# Sheet1.net
KiCad netlist of a schematic drawn in Altium Designer
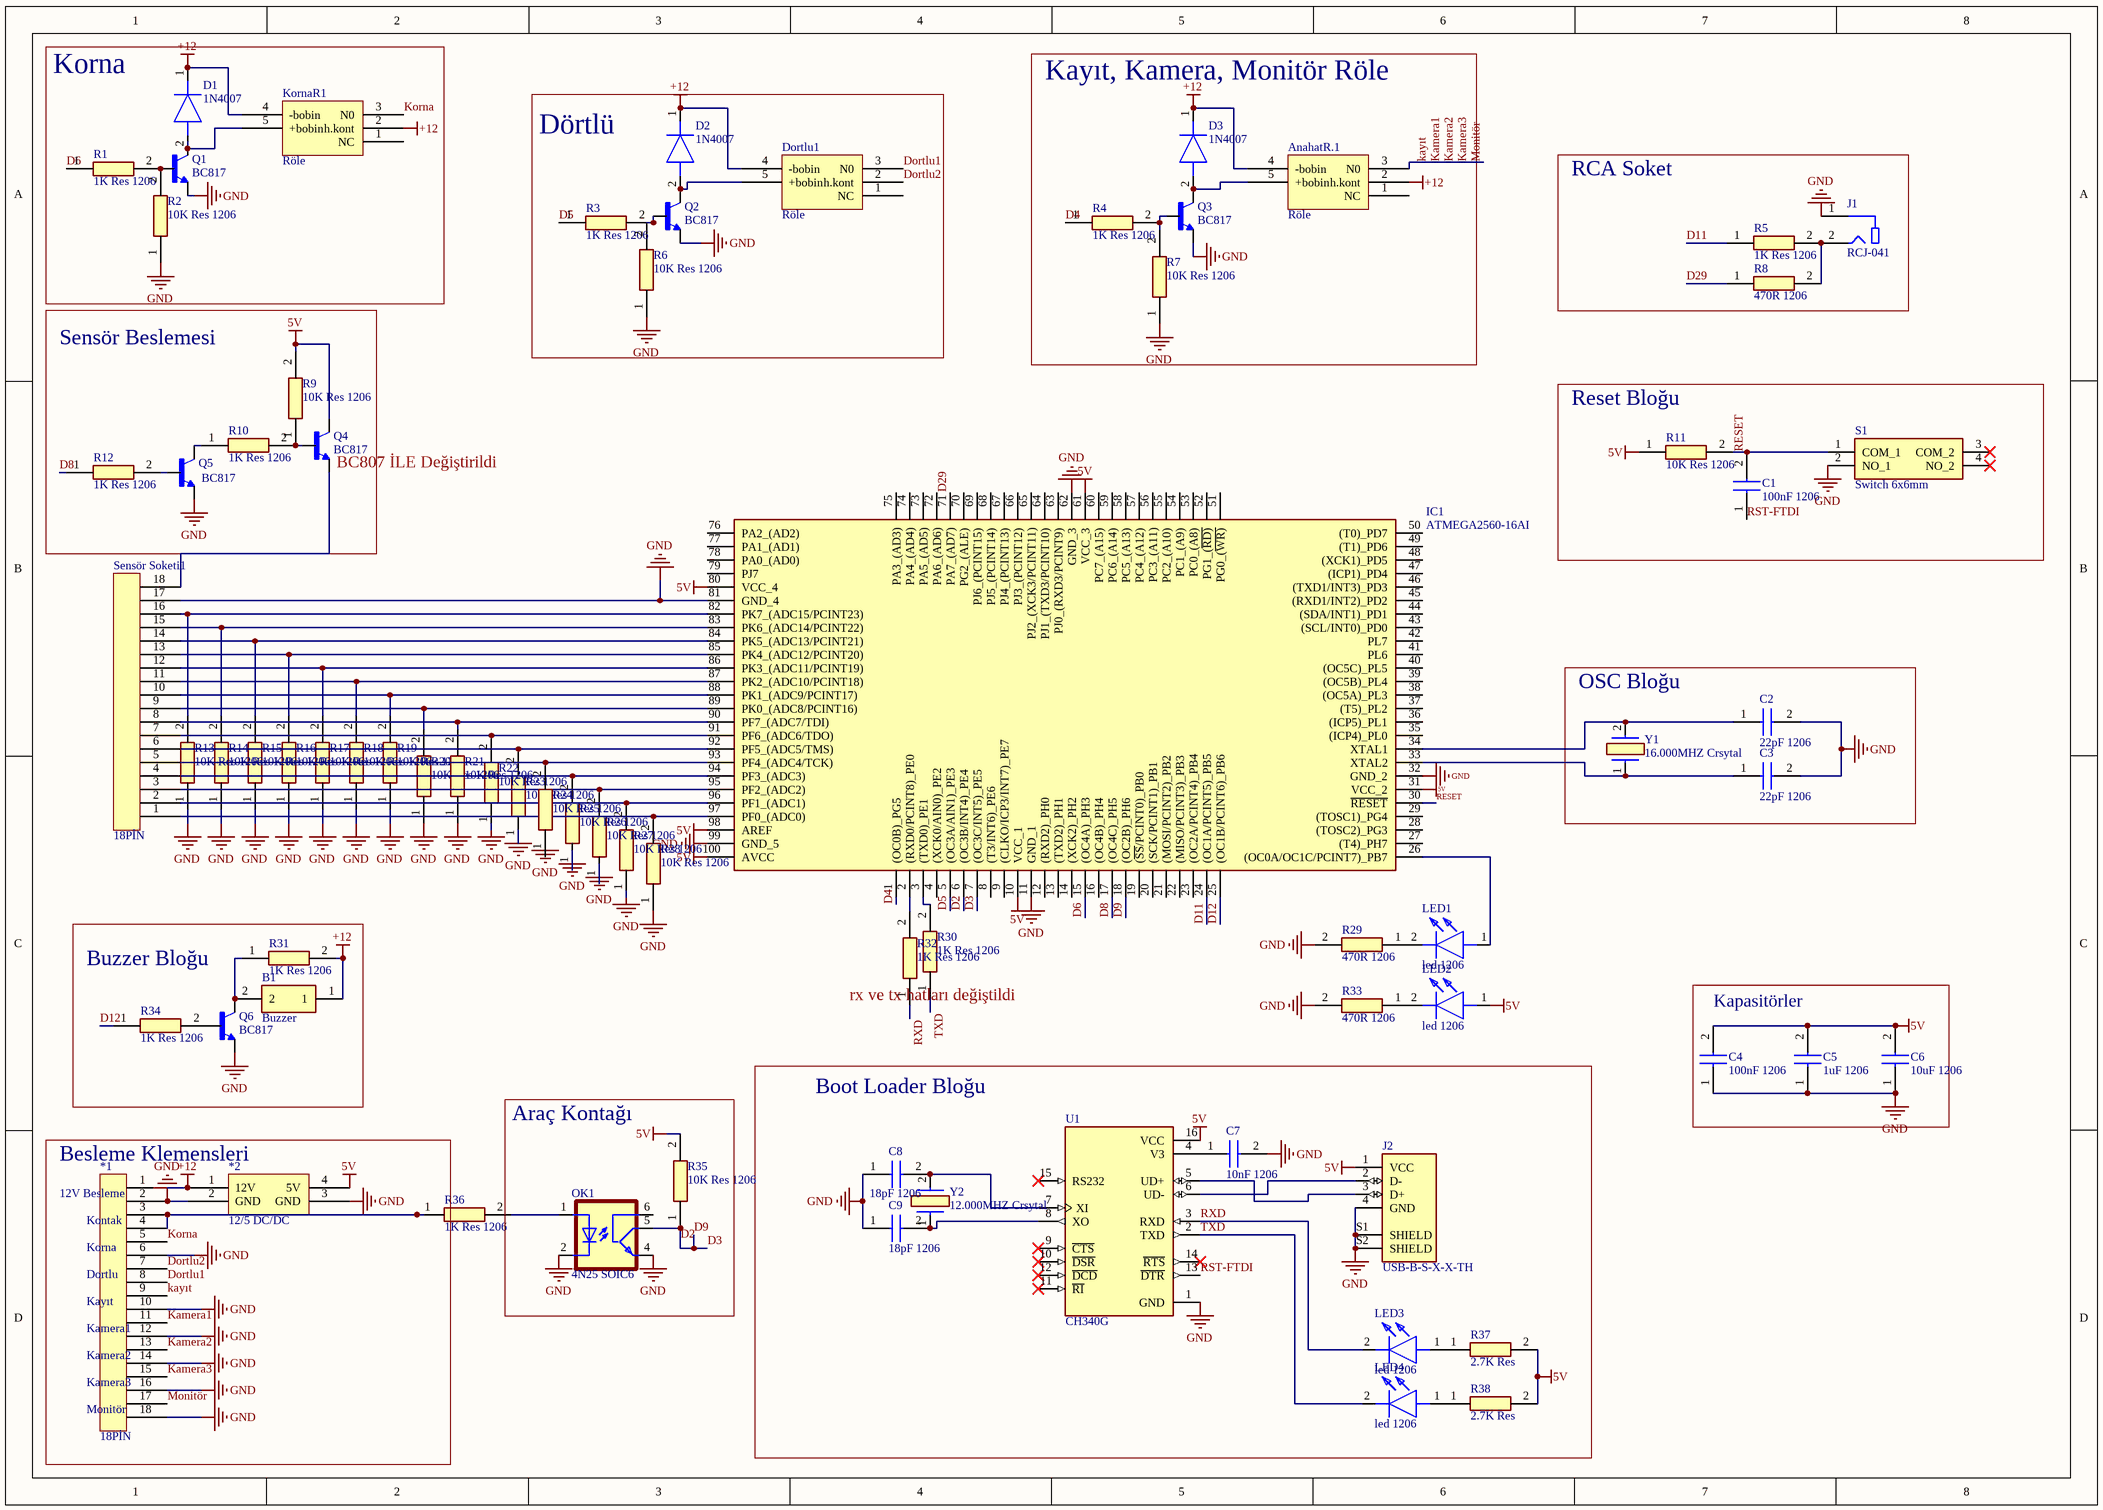
[diagram p0: Sheet1.SchDoc]

(export (version "E")
  (design (tool "Eeschema 10.0.6"))
  (components
    (comp (ref "*1") (value "18PİN") (footprint "18x5,08") (libsource (lib "Schlib1") (part "18PİN")))
    (comp (ref "*2")
      (value "12/5 DC/DC")
      (footprint "12/5V DC/DC")
      (libsource (lib "Schlib1") (part "12/5 DC/DC"))
    )
    (comp (ref "AnahatR.1") (value "Röle") (footprint "Röle") (libsource (lib "Schlib1") (part "Röle")))
    (comp (ref "B1")
      (value "Buzzer")
      (footprint "Buzzer")
      (description "TERMINAL BLOCK,HEADER, 5.08 MM, 2WAY; Product Range:-; Gender:Header")
      (fields (field (name "MF") "TE Connectivity") (field (name "MP") "282814-2"))
      (libsource (lib "Schlib1") (part "Buzzer"))
    )
    (comp (ref "C1")
      (value "100nF 1206")
      (footprint "CAPC3216X95N(100nF 1206)")
      (description "Capacitor")
      (fields
        (field (name "MANUFACTURER_PART_NUMBER") "GRM319F51H104ZA01D")
        (field (name "MOUSER PART NUMBER") "81-GRM319F51H104ZA")
      )
      (libsource (lib "Schlib1") (part "100nF 1206"))
    )
    (comp (ref "C2")
      (value "22pF 1206")
      (footprint "CAPC3216X95N(100nF 1206)")
      (description "Capacitor")
      (fields
        (field (name "MANUFACTURER_PART_NUMBER") "GRM319F51H104ZA01D")
        (field (name "MOUSER PART NUMBER") "81-GRM319F51H104ZA")
      )
      (libsource (lib "Schlib1") (part "22pF 1206"))
    )
    (comp (ref "C3")
      (value "22pF 1206")
      (footprint "CAPC3216X95N(100nF 1206)")
      (description "Capacitor")
      (fields
        (field (name "MANUFACTURER_PART_NUMBER") "GRM319F51H104ZA01D")
        (field (name "MOUSER PART NUMBER") "81-GRM319F51H104ZA")
      )
      (libsource (lib "Schlib1") (part "22pF 1206"))
    )
    (comp (ref "C4")
      (value "100nF 1206")
      (footprint "CAPC3216X95N(100nF 1206)")
      (description "Capacitor")
      (fields
        (field (name "MANUFACTURER_PART_NUMBER") "GRM319F51H104ZA01D")
        (field (name "MOUSER PART NUMBER") "81-GRM319F51H104ZA")
      )
      (libsource (lib "Schlib1") (part "100nF 1206"))
    )
    (comp (ref "C5")
      (value "1uF 1206")
      (footprint "CAPC3216X95N(100nF 1206)")
      (description "Capacitor")
      (fields
        (field (name "MANUFACTURER_PART_NUMBER") "GRM319F51H104ZA01D")
        (field (name "MOUSER PART NUMBER") "81-GRM319F51H104ZA")
      )
      (libsource (lib "Schlib1") (part "1uF 1206"))
    )
    (comp (ref "C6")
      (value "10uF 1206")
      (footprint "CAPC3216X95N(100nF 1206)")
      (description "Capacitor")
      (fields
        (field (name "MANUFACTURER_PART_NUMBER") "GRM319F51H104ZA01D")
        (field (name "MOUSER PART NUMBER") "81-GRM319F51H104ZA")
      )
      (libsource (lib "Schlib1") (part "10uF 1206"))
    )
    (comp (ref "C7")
      (value "10nF 1206")
      (footprint "CAPC3216X95N(100nF 1206)")
      (description "Capacitor")
      (fields
        (field (name "MANUFACTURER_PART_NUMBER") "GRM319F51H104ZA01D")
        (field (name "MOUSER PART NUMBER") "81-GRM319F51H104ZA")
      )
      (libsource (lib "Schlib1") (part "10nF 1206"))
    )
    (comp (ref "C8")
      (value "18pF 1206")
      (footprint "CAPC3216X95N(100nF 1206)")
      (description "Capacitor")
      (fields
        (field (name "MANUFACTURER_PART_NUMBER") "GRM319F51H104ZA01D")
        (field (name "MOUSER PART NUMBER") "81-GRM319F51H104ZA")
      )
      (libsource (lib "Schlib1") (part "18pF 1206"))
    )
    (comp (ref "C9")
      (value "18pF 1206")
      (footprint "CAPC3216X95N(100nF 1206)")
      (description "Capacitor")
      (fields
        (field (name "MANUFACTURER_PART_NUMBER") "GRM319F51H104ZA01D")
        (field (name "MOUSER PART NUMBER") "81-GRM319F51H104ZA")
      )
      (libsource (lib "Schlib1") (part "18pF 1206"))
    )
    (comp (ref "D1")
      (value "1N4007")
      (footprint "1N4007")
      (description "Diode")
      (fields
        (field (name "MANUFACTURER_PART_NUMBER") "1SS400SMT2R")
        (field (name "MOUSER PART NUMBER") "755-1SS400SMT2R")
      )
      (libsource (lib "Schlib1") (part "1N4007"))
    )
    (comp (ref "D2")
      (value "1N4007")
      (footprint "1N4007")
      (description "Diode")
      (fields
        (field (name "MANUFACTURER_PART_NUMBER") "1SS400SMT2R")
        (field (name "MOUSER PART NUMBER") "755-1SS400SMT2R")
      )
      (libsource (lib "Schlib1") (part "1N4007"))
    )
    (comp (ref "D3")
      (value "1N4007")
      (footprint "1N4007")
      (description "Diode")
      (fields
        (field (name "MANUFACTURER_PART_NUMBER") "1SS400SMT2R")
        (field (name "MOUSER PART NUMBER") "755-1SS400SMT2R")
      )
      (libsource (lib "Schlib1") (part "1N4007"))
    )
    (comp (ref "Dortlu1") (value "Röle") (footprint "Röle") (libsource (lib "Schlib1") (part "Röle")))
    (comp (ref "IC1")
      (value "ATMEGA2560-16AI")
      (footprint "QFP50P1600X1600X120-100N")
      (description "Integrated Circuit")
      (fields (field (name "MOUSER PART NUMBER") "556-ATMEGA2560-16AI"))
      (libsource (lib "Schlib1") (part "ATMEGA2560-16AI"))
    )
    (comp (ref "J1")
      (value "RCJ-041")
      (footprint "RCA")
      (description "Metal Right-Angle, RCA Jack, Black Housing and Insulation")
      (fields (field (name "MF") "CUI Devices"))
      (libsource (lib "Schlib1") (part "RCJ-041"))
    )
    (comp (ref "J2")
      (value "USB-B-S-X-X-TH")
      (footprint "USB-B-S-X-X-TH")
      (description "USB-B (USB TYPE-B) USB 2.0 Receptacle Connector 4 Position Through Hole, Right Angle")
      (libsource (lib "Schlib1") (part "USB-B-S-X-X-TH"))
    )
    (comp (ref "KornaR1") (value "Röle") (footprint "Röle") (libsource (lib "Schlib1") (part "Röle")))
    (comp (ref "LED1")
      (value "led 1206")
      (footprint "led 1206")
      (description "LED")
      (fields
        (field (name "MANUFACTURER_PART_NUMBER") "15412085A9000")
        (field (name "MOUSER PART NUMBER") "710-15412085A9000")
      )
      (libsource (lib "Schlib1") (part "led 1206"))
    )
    (comp (ref "LED2")
      (value "led 1206")
      (footprint "led 1206")
      (description "LED")
      (fields
        (field (name "MANUFACTURER_PART_NUMBER") "15412085A9000")
        (field (name "MOUSER PART NUMBER") "710-15412085A9000")
      )
      (libsource (lib "Schlib1") (part "led 1206"))
    )
    (comp (ref "LED3")
      (value "led 1206")
      (footprint "led 1206")
      (description "LED")
      (fields
        (field (name "MANUFACTURER_PART_NUMBER") "15412085A9000")
        (field (name "MOUSER PART NUMBER") "710-15412085A9000")
      )
      (libsource (lib "Schlib1") (part "led 1206"))
    )
    (comp (ref "LED4")
      (value "led 1206")
      (footprint "led 1206")
      (description "LED")
      (fields
        (field (name "MANUFACTURER_PART_NUMBER") "15412085A9000")
        (field (name "MOUSER PART NUMBER") "710-15412085A9000")
      )
      (libsource (lib "Schlib1") (part "led 1206"))
    )
    (comp (ref "OK1")
      (value "4N25 SOIC6")
      (footprint "4N25 SOIC6")
      (description "Optoisolator Transistor with Base Output 4170Vrms 1 Channel 6-SMD")
      (fields (field (name "MP") "4N25SM") (field (name "MF") "ON Semiconductor"))
      (libsource (lib "Schlib1") (part "4N25 SOIC6"))
    )
    (comp (ref "Q1")
      (value "BC817")
      (footprint "BC817 Sot23")
      (description "Bipolar _BJT_ Transistor NPN 45V 500mA 100MHz 300mW Surface Mount SOT-23-3 _TO-236_")
      (fields (field (name "MF") "Nexperia USA"))
      (libsource (lib "Schlib1") (part "BC817"))
    )
    (comp (ref "Q2")
      (value "BC817")
      (footprint "BC817 Sot23")
      (description "Bipolar _BJT_ Transistor NPN 45V 500mA 100MHz 300mW Surface Mount SOT-23-3 _TO-236_")
      (fields (field (name "MF") "Nexperia USA"))
      (libsource (lib "Schlib1") (part "BC817"))
    )
    (comp (ref "Q3")
      (value "BC817")
      (footprint "BC817 Sot23")
      (description "Bipolar _BJT_ Transistor NPN 45V 500mA 100MHz 300mW Surface Mount SOT-23-3 _TO-236_")
      (fields (field (name "MF") "Nexperia USA"))
      (libsource (lib "Schlib1") (part "BC817"))
    )
    (comp (ref "Q4")
      (value "BC817")
      (footprint "BC817 Sot23")
      (description "Bipolar _BJT_ Transistor NPN 45V 500mA 100MHz 300mW Surface Mount SOT-23-3 _TO-236_")
      (fields (field (name "MF") "Nexperia USA"))
      (libsource (lib "Schlib1") (part "BC817"))
    )
    (comp (ref "Q5")
      (value "BC817")
      (footprint "BC817 Sot23")
      (description "Bipolar _BJT_ Transistor NPN 45V 500mA 100MHz 300mW Surface Mount SOT-23-3 _TO-236_")
      (fields (field (name "MF") "Nexperia USA"))
      (libsource (lib "Schlib1") (part "BC817"))
    )
    (comp (ref "Q6")
      (value "BC817")
      (footprint "BC817 Sot23")
      (description "Bipolar _BJT_ Transistor NPN 45V 500mA 100MHz 300mW Surface Mount SOT-23-3 _TO-236_")
      (fields (field (name "MF") "Nexperia USA"))
      (libsource (lib "Schlib1") (part "BC817"))
    )
    (comp (ref "R1")
      (value "1K Res 1206")
      (footprint "RESC3216X60N ( 1206 )")
      (description "Resistor")
      (fields
        (field (name "MANUFACTURER_PART_NUMBER") "CRCW120610K0DHEAP")
        (field (name "MOUSER PART NUMBER") "71-CRCW120610K0DHEAP")
      )
      (libsource (lib "Schlib1") (part "1K Res 1206"))
    )
    (comp (ref "R2")
      (value "10K Res 1206")
      (footprint "RESC3216X60N ( 1206 )")
      (description "Resistor")
      (fields
        (field (name "MANUFACTURER_PART_NUMBER") "CRCW120610K0DHEAP")
        (field (name "MOUSER PART NUMBER") "71-CRCW120610K0DHEAP")
      )
      (libsource (lib "Schlib1") (part "10K Res 1206"))
    )
    (comp (ref "R3")
      (value "1K Res 1206")
      (footprint "RESC3216X60N ( 1206 )")
      (description "Resistor")
      (fields
        (field (name "MANUFACTURER_PART_NUMBER") "CRCW120610K0DHEAP")
        (field (name "MOUSER PART NUMBER") "71-CRCW120610K0DHEAP")
      )
      (libsource (lib "Schlib1") (part "1K Res 1206"))
    )
    (comp (ref "R4")
      (value "1K Res 1206")
      (footprint "RESC3216X60N ( 1206 )")
      (description "Resistor")
      (fields
        (field (name "MANUFACTURER_PART_NUMBER") "CRCW120610K0DHEAP")
        (field (name "MOUSER PART NUMBER") "71-CRCW120610K0DHEAP")
      )
      (libsource (lib "Schlib1") (part "1K Res 1206"))
    )
    (comp (ref "R5")
      (value "1K Res 1206")
      (footprint "RESC3216X60N ( 1206 )")
      (description "Resistor")
      (fields
        (field (name "MANUFACTURER_PART_NUMBER") "CRCW120610K0DHEAP")
        (field (name "MOUSER PART NUMBER") "71-CRCW120610K0DHEAP")
      )
      (libsource (lib "Schlib1") (part "1K Res 1206"))
    )
    (comp (ref "R6")
      (value "10K Res 1206")
      (footprint "RESC3216X60N ( 1206 )")
      (description "Resistor")
      (fields
        (field (name "MANUFACTURER_PART_NUMBER") "CRCW120610K0DHEAP")
        (field (name "MOUSER PART NUMBER") "71-CRCW120610K0DHEAP")
      )
      (libsource (lib "Schlib1") (part "10K Res 1206"))
    )
    (comp (ref "R7")
      (value "10K Res 1206")
      (footprint "RESC3216X60N ( 1206 )")
      (description "Resistor")
      (fields
        (field (name "MANUFACTURER_PART_NUMBER") "CRCW120610K0DHEAP")
        (field (name "MOUSER PART NUMBER") "71-CRCW120610K0DHEAP")
      )
      (libsource (lib "Schlib1") (part "10K Res 1206"))
    )
    (comp (ref "R8")
      (value "470R 1206")
      (footprint "RESC3216X60N ( 1206 )")
      (description "Resistor")
      (fields
        (field (name "MANUFACTURER_PART_NUMBER") "CRCW120610K0DHEAP")
        (field (name "MOUSER PART NUMBER") "71-CRCW120610K0DHEAP")
      )
      (libsource (lib "Schlib1") (part "470R 1206"))
    )
    (comp (ref "R9")
      (value "10K Res 1206")
      (footprint "RESC3216X60N ( 1206 )")
      (description "Resistor")
      (fields
        (field (name "MANUFACTURER_PART_NUMBER") "CRCW120610K0DHEAP")
        (field (name "MOUSER PART NUMBER") "71-CRCW120610K0DHEAP")
      )
      (libsource (lib "Schlib1") (part "10K Res 1206"))
    )
    (comp (ref "R10")
      (value "1K Res 1206")
      (footprint "RESC3216X60N ( 1206 )")
      (description "Resistor")
      (fields
        (field (name "MANUFACTURER_PART_NUMBER") "CRCW120610K0DHEAP")
        (field (name "MOUSER PART NUMBER") "71-CRCW120610K0DHEAP")
      )
      (libsource (lib "Schlib1") (part "1K Res 1206"))
    )
    (comp (ref "R11")
      (value "10K Res 1206")
      (footprint "RESC3216X60N ( 1206 )")
      (description "Resistor")
      (fields
        (field (name "MANUFACTURER_PART_NUMBER") "CRCW120610K0DHEAP")
        (field (name "MOUSER PART NUMBER") "71-CRCW120610K0DHEAP")
      )
      (libsource (lib "") (part "10K Res 1206_1"))
    )
    (comp (ref "R12")
      (value "1K Res 1206")
      (footprint "RESC3216X60N ( 1206 )")
      (description "Resistor")
      (fields
        (field (name "MANUFACTURER_PART_NUMBER") "CRCW120610K0DHEAP")
        (field (name "MOUSER PART NUMBER") "71-CRCW120610K0DHEAP")
      )
      (libsource (lib "Schlib1") (part "1K Res 1206"))
    )
    (comp (ref "R13")
      (value "10K Res 1206")
      (footprint "RESC3216X60N ( 1206 )")
      (description "Resistor")
      (fields
        (field (name "MANUFACTURER_PART_NUMBER") "CRCW120610K0DHEAP")
        (field (name "MOUSER PART NUMBER") "71-CRCW120610K0DHEAP")
      )
      (libsource (lib "Schlib1") (part "10K Res 1206"))
    )
    (comp (ref "R14")
      (value "10K Res 1206")
      (footprint "RESC3216X60N ( 1206 )")
      (description "Resistor")
      (fields
        (field (name "MANUFACTURER_PART_NUMBER") "CRCW120610K0DHEAP")
        (field (name "MOUSER PART NUMBER") "71-CRCW120610K0DHEAP")
      )
      (libsource (lib "Schlib1") (part "10K Res 1206"))
    )
    (comp (ref "R15")
      (value "10K Res 1206")
      (footprint "RESC3216X60N ( 1206 )")
      (description "Resistor")
      (fields
        (field (name "MANUFACTURER_PART_NUMBER") "CRCW120610K0DHEAP")
        (field (name "MOUSER PART NUMBER") "71-CRCW120610K0DHEAP")
      )
      (libsource (lib "Schlib1") (part "10K Res 1206"))
    )
    (comp (ref "R16")
      (value "10K Res 1206")
      (footprint "RESC3216X60N ( 1206 )")
      (description "Resistor")
      (fields
        (field (name "MANUFACTURER_PART_NUMBER") "CRCW120610K0DHEAP")
        (field (name "MOUSER PART NUMBER") "71-CRCW120610K0DHEAP")
      )
      (libsource (lib "Schlib1") (part "10K Res 1206"))
    )
    (comp (ref "R17")
      (value "10K Res 1206")
      (footprint "RESC3216X60N ( 1206 )")
      (description "Resistor")
      (fields
        (field (name "MANUFACTURER_PART_NUMBER") "CRCW120610K0DHEAP")
        (field (name "MOUSER PART NUMBER") "71-CRCW120610K0DHEAP")
      )
      (libsource (lib "Schlib1") (part "10K Res 1206"))
    )
    (comp (ref "R18")
      (value "10K Res 1206")
      (footprint "RESC3216X60N ( 1206 )")
      (description "Resistor")
      (fields
        (field (name "MANUFACTURER_PART_NUMBER") "CRCW120610K0DHEAP")
        (field (name "MOUSER PART NUMBER") "71-CRCW120610K0DHEAP")
      )
      (libsource (lib "Schlib1") (part "10K Res 1206"))
    )
    (comp (ref "R19")
      (value "10K Res 1206")
      (footprint "RESC3216X60N ( 1206 )")
      (description "Resistor")
      (fields
        (field (name "MANUFACTURER_PART_NUMBER") "CRCW120610K0DHEAP")
        (field (name "MOUSER PART NUMBER") "71-CRCW120610K0DHEAP")
      )
      (libsource (lib "Schlib1") (part "10K Res 1206"))
    )
    (comp (ref "R20")
      (value "10K Res 1206")
      (footprint "RESC3216X60N ( 1206 )")
      (description "Resistor")
      (fields
        (field (name "MANUFACTURER_PART_NUMBER") "CRCW120610K0DHEAP")
        (field (name "MOUSER PART NUMBER") "71-CRCW120610K0DHEAP")
      )
      (libsource (lib "Schlib1") (part "10K Res 1206"))
    )
    (comp (ref "R21")
      (value "10K Res 1206")
      (footprint "RESC3216X60N ( 1206 )")
      (description "Resistor")
      (fields
        (field (name "MANUFACTURER_PART_NUMBER") "CRCW120610K0DHEAP")
        (field (name "MOUSER PART NUMBER") "71-CRCW120610K0DHEAP")
      )
      (libsource (lib "Schlib1") (part "10K Res 1206"))
    )
    (comp (ref "R22")
      (value "10K Res 1206")
      (footprint "RESC3216X60N ( 1206 )")
      (description "Resistor")
      (fields
        (field (name "MANUFACTURER_PART_NUMBER") "CRCW120610K0DHEAP")
        (field (name "MOUSER PART NUMBER") "71-CRCW120610K0DHEAP")
      )
      (libsource (lib "Schlib1") (part "10K Res 1206"))
    )
    (comp (ref "R23")
      (value "10K Res 1206")
      (footprint "RESC3216X60N ( 1206 )")
      (description "Resistor")
      (fields
        (field (name "MANUFACTURER_PART_NUMBER") "CRCW120610K0DHEAP")
        (field (name "MOUSER PART NUMBER") "71-CRCW120610K0DHEAP")
      )
      (libsource (lib "Schlib1") (part "10K Res 1206"))
    )
    (comp (ref "R24")
      (value "10K Res 1206")
      (footprint "RESC3216X60N ( 1206 )")
      (description "Resistor")
      (fields
        (field (name "MANUFACTURER_PART_NUMBER") "CRCW120610K0DHEAP")
        (field (name "MOUSER PART NUMBER") "71-CRCW120610K0DHEAP")
      )
      (libsource (lib "Schlib1") (part "10K Res 1206"))
    )
    (comp (ref "R25")
      (value "10K Res 1206")
      (footprint "RESC3216X60N ( 1206 )")
      (description "Resistor")
      (fields
        (field (name "MANUFACTURER_PART_NUMBER") "CRCW120610K0DHEAP")
        (field (name "MOUSER PART NUMBER") "71-CRCW120610K0DHEAP")
      )
      (libsource (lib "Schlib1") (part "10K Res 1206"))
    )
    (comp (ref "R26")
      (value "10K Res 1206")
      (footprint "RESC3216X60N ( 1206 )")
      (description "Resistor")
      (fields
        (field (name "MANUFACTURER_PART_NUMBER") "CRCW120610K0DHEAP")
        (field (name "MOUSER PART NUMBER") "71-CRCW120610K0DHEAP")
      )
      (libsource (lib "Schlib1") (part "10K Res 1206"))
    )
    (comp (ref "R27")
      (value "10K Res 1206")
      (footprint "RESC3216X60N ( 1206 )")
      (description "Resistor")
      (fields
        (field (name "MANUFACTURER_PART_NUMBER") "CRCW120610K0DHEAP")
        (field (name "MOUSER PART NUMBER") "71-CRCW120610K0DHEAP")
      )
      (libsource (lib "Schlib1") (part "10K Res 1206"))
    )
    (comp (ref "R28")
      (value "10K Res 1206")
      (footprint "RESC3216X60N ( 1206 )")
      (description "Resistor")
      (fields
        (field (name "MANUFACTURER_PART_NUMBER") "CRCW120610K0DHEAP")
        (field (name "MOUSER PART NUMBER") "71-CRCW120610K0DHEAP")
      )
      (libsource (lib "Schlib1") (part "10K Res 1206"))
    )
    (comp (ref "R29")
      (value "470R 1206")
      (footprint "RESC3216X60N ( 1206 )")
      (description "Resistor")
      (fields
        (field (name "MANUFACTURER_PART_NUMBER") "CRCW120610K0DHEAP")
        (field (name "MOUSER PART NUMBER") "71-CRCW120610K0DHEAP")
      )
      (libsource (lib "") (part "470R 1206_1"))
    )
    (comp (ref "R30")
      (value "1K Res 1206")
      (footprint "RESC3216X60N ( 1206 )")
      (description "Resistor")
      (fields
        (field (name "MANUFACTURER_PART_NUMBER") "CRCW120610K0DHEAP")
        (field (name "MOUSER PART NUMBER") "71-CRCW120610K0DHEAP")
      )
      (libsource (lib "") (part "1K Res 1206_1"))
    )
    (comp (ref "R31")
      (value "1K Res 1206")
      (footprint "RESC3216X60N ( 1206 )")
      (description "Resistor")
      (fields
        (field (name "MANUFACTURER_PART_NUMBER") "CRCW120610K0DHEAP")
        (field (name "MOUSER PART NUMBER") "71-CRCW120610K0DHEAP")
      )
      (libsource (lib "Schlib1") (part "1K Res 1206"))
    )
    (comp (ref "R32")
      (value "1K Res 1206")
      (footprint "RESC3216X60N ( 1206 )")
      (description "Resistor")
      (fields
        (field (name "MANUFACTURER_PART_NUMBER") "CRCW120610K0DHEAP")
        (field (name "MOUSER PART NUMBER") "71-CRCW120610K0DHEAP")
      )
      (libsource (lib "") (part "1K Res 1206_1"))
    )
    (comp (ref "R33")
      (value "470R 1206")
      (footprint "RESC3216X60N ( 1206 )")
      (description "Resistor")
      (fields
        (field (name "MANUFACTURER_PART_NUMBER") "CRCW120610K0DHEAP")
        (field (name "MOUSER PART NUMBER") "71-CRCW120610K0DHEAP")
      )
      (libsource (lib "") (part "470R 1206_1"))
    )
    (comp (ref "R34")
      (value "1K Res 1206")
      (footprint "RESC3216X60N ( 1206 )")
      (description "Resistor")
      (fields
        (field (name "MANUFACTURER_PART_NUMBER") "CRCW120610K0DHEAP")
        (field (name "MOUSER PART NUMBER") "71-CRCW120610K0DHEAP")
      )
      (libsource (lib "Schlib1") (part "1K Res 1206"))
    )
    (comp (ref "R35")
      (value "10K Res 1206")
      (footprint "RESC3216X60N ( 1206 )")
      (description "Resistor")
      (fields
        (field (name "MANUFACTURER_PART_NUMBER") "CRCW120610K0DHEAP")
        (field (name "MOUSER PART NUMBER") "71-CRCW120610K0DHEAP")
      )
      (libsource (lib "Schlib1") (part "10K Res 1206"))
    )
    (comp (ref "R36")
      (value "1K Res 1206")
      (footprint "RESC3216X60N ( 1206 )")
      (description "Resistor")
      (fields
        (field (name "MANUFACTURER_PART_NUMBER") "CRCW120610K0DHEAP")
        (field (name "MOUSER PART NUMBER") "71-CRCW120610K0DHEAP")
      )
      (libsource (lib "Schlib1") (part "1K Res 1206"))
    )
    (comp (ref "R37")
      (value "2.7K Res")
      (footprint "RESC3216X60N ( 1206 )")
      (description "Resistor")
      (fields
        (field (name "MANUFACTURER_PART_NUMBER") "CRCW120610K0DHEAP")
        (field (name "MOUSER PART NUMBER") "71-CRCW120610K0DHEAP")
      )
      (libsource (lib "Schlib1") (part "2.7K Res"))
    )
    (comp (ref "R38")
      (value "2.7K Res")
      (footprint "RESC3216X60N ( 1206 )")
      (description "Resistor")
      (fields
        (field (name "MANUFACTURER_PART_NUMBER") "CRCW120610K0DHEAP")
        (field (name "MOUSER PART NUMBER") "71-CRCW120610K0DHEAP")
      )
      (libsource (lib "Schlib1") (part "2.7K Res"))
    )
    (comp (ref "S1")
      (value "Switch 6x6mm")
      (footprint "6x6x8mm Push Buton")
      (description "Switch")
      (fields
        (field (name "MANUFACTURER_PART_NUMBER") "430182070816")
        (field (name "MOUSER PART NUMBER") "710-430182070816")
      )
      (libsource (lib "Schlib1") (part "Switch 6x6mm"))
    )
    (comp (ref "Sensör Soketi1") (value "18PİN") (footprint "18x5,08") (libsource (lib "") (part "18PİN_1")))
    (comp (ref "U1") (value "CH340G") (footprint "SOIC16") (libsource (lib "Schlib1") (part "CH340G")))
    (comp (ref "Y1")
      (value "16.000MHZ Crsytal")
      (footprint "XTAL_Dip")
      (description "Crystal or Oscillator")
      (fields
        (field (name "MANUFACTURER_PART_NUMBER") "ABLS2-16.000MHZ-D4Y-T")
        (field (name "MOUSER PART NUMBER") "815-ABLS2-16-D4Y-T")
      )
      (libsource (lib "Schlib1") (part "16.000MHZ Crsytal"))
    )
    (comp (ref "Y2")
      (value "12.000MHZ Crsytal")
      (footprint "XTAL_Dip")
      (description "Crystal or Oscillator")
      (fields
        (field (name "MANUFACTURER_PART_NUMBER") "ABLS2-16.000MHZ-D4Y-T")
        (field (name "MOUSER PART NUMBER") "815-ABLS2-16-D4Y-T")
      )
      (libsource (lib "Schlib1") (part "12.000MHZ Crsytal"))
    )
  )
  (nets
    (net (code "1") (name "+12") (class "Default")
      (node (ref "*1") (pin "1") (pintype "passive"))
      (node (ref "*2") (pin "1") (pinfunction "12V_1") (pintype "passive"))
      (node (ref "AnahatR.1") (pin "2") (pinfunction "h.kont_2") (pintype "passive"))
      (node (ref "AnahatR.1") (pin "4") (pinfunction "-bobin_4") (pintype "passive"))
      (node (ref "B1") (pin "1") (pinfunction "1_1") (pintype "passive"))
      (node (ref "D1") (pin "1") (pinfunction "K_1") (pintype "passive"))
      (node (ref "D2") (pin "1") (pinfunction "K_1") (pintype "passive"))
      (node (ref "D3") (pin "1") (pinfunction "K_1") (pintype "passive"))
      (node (ref "Dortlu1") (pin "4") (pinfunction "-bobin_4") (pintype "passive"))
      (node (ref "KornaR1") (pin "2") (pinfunction "h.kont_2") (pintype "passive"))
      (node (ref "KornaR1") (pin "4") (pinfunction "-bobin_4") (pintype "passive"))
      (node (ref "R31") (pin "2") (pinfunction "2_2") (pintype "passive"))
    )
    (net (code "2") (name "/D2") (class "Default")
      (node (ref "IC1") (pin "18") (pinfunction "(OC2B)_PH6_18") (pintype "passive"))
      (node (ref "IC1") (pin "6") (pinfunction "(OC3B/INT4)_PE4_6") (pintype "passive"))
      (node (ref "IC1") (pin "7") (pinfunction "(OC3C/INT5)_PE5_7") (pintype "passive"))
      (node (ref "OK1") (pin "5") (pinfunction "COL_5") (pintype "passive"))
      (node (ref "R35") (pin "1") (pinfunction "1_1") (pintype "passive"))
    )
    (net (code "3") (name "/D4") (class "Default")
      (node (ref "IC1") (pin "1") (pinfunction "(OC0B)_PG5_1") (pintype "passive"))
      (node (ref "R4") (pin "1") (pinfunction "1_1") (pintype "passive"))
    )
    (net (code "4") (name "/D5") (class "Default")
      (node (ref "IC1") (pin "5") (pinfunction "(OC3A/AIN1)_PE3_5") (pintype "passive"))
      (node (ref "R3") (pin "1") (pinfunction "1_1") (pintype "passive"))
    )
    (net (code "5") (name "/D6") (class "Default")
      (node (ref "IC1") (pin "15") (pinfunction "(OC4A)_PH3_15") (pintype "passive"))
      (node (ref "R1") (pin "1") (pinfunction "1_1") (pintype "passive"))
    )
    (net (code "6") (name "/D8") (class "Default")
      (node (ref "IC1") (pin "17") (pinfunction "(OC4C)_PH5_17") (pintype "passive"))
      (node (ref "R12") (pin "1") (pinfunction "1_1") (pintype "passive"))
    )
    (net (code "7") (name "/D11") (class "Default")
      (node (ref "IC1") (pin "24") (pinfunction "(OC1A/PCINT5)_PB5_24") (pintype "passive"))
      (node (ref "R5") (pin "1") (pinfunction "1_1") (pintype "passive"))
    )
    (net (code "8") (name "/D12") (class "Default")
      (node (ref "IC1") (pin "25") (pinfunction "(OC1B/PCINT6)_PB6_25") (pintype "passive"))
      (node (ref "R34") (pin "1") (pinfunction "1_1") (pintype "passive"))
    )
    (net (code "9") (name "/D29") (class "Default")
      (node (ref "IC1") (pin "71") (pinfunction "PA7_(AD7)_71") (pintype "passive"))
      (node (ref "R8") (pin "1") (pinfunction "1_1") (pintype "passive"))
    )
    (net (code "10") (name "/Dortlu1") (class "Default")
      (node (ref "*1") (pin "8") (pintype "passive"))
      (node (ref "Dortlu1") (pin "3") (pinfunction "N0_3") (pintype "passive"))
    )
    (net (code "11") (name "/Dortlu2") (class "Default")
      (node (ref "*1") (pin "7") (pintype "passive"))
      (node (ref "Dortlu1") (pin "2") (pinfunction "h.kont_2") (pintype "passive"))
    )
    (net (code "12") (name "/Kamera1") (class "Default")
      (node (ref "*1") (pin "11") (pintype "passive"))
      (node (ref "*1") (pin "13") (pintype "passive"))
      (node (ref "*1") (pin "15") (pintype "passive"))
      (node (ref "*1") (pin "17") (pintype "passive"))
      (node (ref "*1") (pin "9") (pintype "passive"))
      (node (ref "AnahatR.1") (pin "3") (pinfunction "N0_3") (pintype "passive"))
    )
    (net (code "13") (name "/Korna") (class "Default")
      (node (ref "*1") (pin "5") (pintype "passive"))
      (node (ref "KornaR1") (pin "3") (pinfunction "N0_3") (pintype "passive"))
    )
    (net (code "14") (name "/RESET") (class "Default")
      (node (ref "C1") (pin "2") (pinfunction "2_2") (pintype "passive"))
      (node (ref "IC1") (pin "30") (pinfunction "~{RESET}_30") (pintype "passive"))
      (node (ref "R11") (pin "2") (pinfunction "2_2") (pintype "passive"))
      (node (ref "S1") (pin "1") (pinfunction "COM_1_1") (pintype "passive"))
    )
    (net (code "15") (name "/RST-FTDI") (class "Default")
      (node (ref "C1") (pin "1") (pinfunction "1_1") (pintype "passive"))
      (node (ref "U1") (pin "13") (pinfunction "~{DTR}_13") (pintype "output"))
    )
    (net (code "16") (name "/RXD") (class "Default")
      (node (ref "LED3") (pin "2") (pinfunction "K_2") (pintype "passive"))
      (node (ref "R32") (pin "1") (pinfunction "1_1") (pintype "passive"))
      (node (ref "U1") (pin "3") (pinfunction "RXD_3") (pintype "input"))
    )
    (net (code "17") (name "/TXD") (class "Default")
      (node (ref "LED4") (pin "2") (pinfunction "K_2") (pintype "passive"))
      (node (ref "R30") (pin "1") (pinfunction "1_1") (pintype "passive"))
      (node (ref "U1") (pin "2") (pinfunction "TXD_2") (pintype "output"))
    )
    (net (code "18") (name "5V") (class "Default")
      (node (ref "*2") (pin "4") (pinfunction "5V_4") (pintype "passive"))
      (node (ref "C4") (pin "2") (pinfunction "2_2") (pintype "passive"))
      (node (ref "C5") (pin "2") (pinfunction "2_2") (pintype "passive"))
      (node (ref "C6") (pin "2") (pinfunction "2_2") (pintype "passive"))
      (node (ref "IC1") (pin "10") (pinfunction "VCC_1_10") (pintype "passive"))
      (node (ref "IC1") (pin "100") (pinfunction "AVCC_100") (pintype "passive"))
      (node (ref "IC1") (pin "31") (pinfunction "VCC_2_31") (pintype "passive"))
      (node (ref "IC1") (pin "61") (pinfunction "VCC_3_61") (pintype "passive"))
      (node (ref "IC1") (pin "80") (pinfunction "VCC_4_80") (pintype "passive"))
      (node (ref "IC1") (pin "98") (pinfunction "AREF_98") (pintype "passive"))
      (node (ref "J2") (pin "1") (pinfunction "VCC_1") (pintype "power_in"))
      (node (ref "LED2") (pin "1") (pinfunction "A_1") (pintype "passive"))
      (node (ref "Q4") (pin "3") (pinfunction "C_3") (pintype "passive"))
      (node (ref "R11") (pin "1") (pinfunction "1_1") (pintype "passive"))
      (node (ref "R35") (pin "2") (pinfunction "2_2") (pintype "passive"))
      (node (ref "R37") (pin "2") (pinfunction "2_2") (pintype "passive"))
      (node (ref "R38") (pin "2") (pinfunction "2_2") (pintype "passive"))
      (node (ref "R9") (pin "2") (pinfunction "2_2") (pintype "passive"))
      (node (ref "U1") (pin "16") (pinfunction "VCC_16") (pintype "power_in"))
    )
    (net (code "19") (name "GND") (class "Default")
      (node (ref "*1") (pin "10") (pintype "passive"))
      (node (ref "*1") (pin "12") (pintype "passive"))
      (node (ref "*1") (pin "14") (pintype "passive"))
      (node (ref "*1") (pin "16") (pintype "passive"))
      (node (ref "*1") (pin "18") (pintype "passive"))
      (node (ref "*1") (pin "2") (pintype "passive"))
      (node (ref "*1") (pin "6") (pintype "passive"))
      (node (ref "*2") (pin "2") (pinfunction "GND_2") (pintype "passive"))
      (node (ref "*2") (pin "3") (pinfunction "GND_3") (pintype "passive"))
      (node (ref "C2") (pin "2") (pinfunction "2_2") (pintype "passive"))
      (node (ref "C3") (pin "2") (pinfunction "2_2") (pintype "passive"))
      (node (ref "C4") (pin "1") (pinfunction "1_1") (pintype "passive"))
      (node (ref "C5") (pin "1") (pinfunction "1_1") (pintype "passive"))
      (node (ref "C6") (pin "1") (pinfunction "1_1") (pintype "passive"))
      (node (ref "C7") (pin "2") (pinfunction "2_2") (pintype "passive"))
      (node (ref "C8") (pin "1") (pinfunction "1_1") (pintype "passive"))
      (node (ref "C9") (pin "1") (pinfunction "1_1") (pintype "passive"))
      (node (ref "IC1") (pin "11") (pinfunction "GND_1_11") (pintype "passive"))
      (node (ref "IC1") (pin "32") (pinfunction "GND_2_32") (pintype "passive"))
      (node (ref "IC1") (pin "62") (pinfunction "GND_3_62") (pintype "passive"))
      (node (ref "IC1") (pin "81") (pinfunction "GND_4_81") (pintype "passive"))
      (node (ref "IC1") (pin "99") (pinfunction "GND_5_99") (pintype "passive"))
      (node (ref "J1") (pin "1") (pinfunction "1_1") (pintype "passive"))
      (node (ref "J2") (pin "4") (pinfunction "GND_4") (pintype "power_in"))
      (node (ref "J2") (pin "S1") (pinfunction "SHIELD_S1") (pintype "passive"))
      (node (ref "J2") (pin "S2") (pinfunction "SHIELD_S2") (pintype "passive"))
      (node (ref "OK1") (pin "2") (pinfunction "C_2") (pintype "passive"))
      (node (ref "OK1") (pin "4") (pinfunction "EMI_4") (pintype "passive"))
      (node (ref "Q1") (pin "2") (pinfunction "E_2") (pintype "passive"))
      (node (ref "Q2") (pin "2") (pinfunction "E_2") (pintype "passive"))
      (node (ref "Q3") (pin "2") (pinfunction "E_2") (pintype "passive"))
      (node (ref "Q5") (pin "2") (pinfunction "E_2") (pintype "passive"))
      (node (ref "Q6") (pin "2") (pinfunction "E_2") (pintype "passive"))
      (node (ref "R13") (pin "1") (pinfunction "1_1") (pintype "passive"))
      (node (ref "R14") (pin "1") (pinfunction "1_1") (pintype "passive"))
      (node (ref "R15") (pin "1") (pinfunction "1_1") (pintype "passive"))
      (node (ref "R16") (pin "1") (pinfunction "1_1") (pintype "passive"))
      (node (ref "R17") (pin "1") (pinfunction "1_1") (pintype "passive"))
      (node (ref "R18") (pin "1") (pinfunction "1_1") (pintype "passive"))
      (node (ref "R19") (pin "1") (pinfunction "1_1") (pintype "passive"))
      (node (ref "R2") (pin "1") (pinfunction "1_1") (pintype "passive"))
      (node (ref "R20") (pin "1") (pinfunction "1_1") (pintype "passive"))
      (node (ref "R21") (pin "1") (pinfunction "1_1") (pintype "passive"))
      (node (ref "R22") (pin "1") (pinfunction "1_1") (pintype "passive"))
      (node (ref "R23") (pin "1") (pinfunction "1_1") (pintype "passive"))
      (node (ref "R24") (pin "1") (pinfunction "1_1") (pintype "passive"))
      (node (ref "R25") (pin "1") (pinfunction "1_1") (pintype "passive"))
      (node (ref "R26") (pin "1") (pinfunction "1_1") (pintype "passive"))
      (node (ref "R27") (pin "1") (pinfunction "1_1") (pintype "passive"))
      (node (ref "R28") (pin "1") (pinfunction "1_1") (pintype "passive"))
      (node (ref "R29") (pin "2") (pinfunction "2_2") (pintype "passive"))
      (node (ref "R33") (pin "2") (pinfunction "2_2") (pintype "passive"))
      (node (ref "R6") (pin "1") (pinfunction "1_1") (pintype "passive"))
      (node (ref "R7") (pin "1") (pinfunction "1_1") (pintype "passive"))
      (node (ref "S1") (pin "2") (pinfunction "NO_1_2") (pintype "passive"))
      (node (ref "Sensör Soketi1") (pin "17") (pintype "passive"))
      (node (ref "U1") (pin "1") (pinfunction "GND_1") (pintype "power_in"))
    )
    (net (code "20") (name "Net-(*1-Pad3)") (class "Default")
      (node (ref "*1") (pin "3") (pintype "passive"))
      (node (ref "*1") (pin "4") (pintype "passive"))
      (node (ref "R36") (pin "1") (pinfunction "1_1") (pintype "passive"))
    )
    (net (code "21") (name "Net-(AnahatR.1-+bobin)") (class "Default")
      (node (ref "AnahatR.1") (pin "5") (pinfunction "+bobin_5") (pintype "passive"))
      (node (ref "D3") (pin "2") (pinfunction "A_2") (pintype "passive"))
      (node (ref "Q3") (pin "3") (pinfunction "C_3") (pintype "passive"))
    )
    (net (code "22") (name "Net-(D1-A)") (class "Default")
      (node (ref "D1") (pin "2") (pinfunction "A_2") (pintype "passive"))
      (node (ref "KornaR1") (pin "5") (pinfunction "+bobin_5") (pintype "passive"))
      (node (ref "Q1") (pin "3") (pinfunction "C_3") (pintype "passive"))
    )
    (net (code "23") (name "Net-(D2-A)") (class "Default")
      (node (ref "D2") (pin "2") (pinfunction "A_2") (pintype "passive"))
      (node (ref "Dortlu1") (pin "5") (pinfunction "+bobin_5") (pintype "passive"))
      (node (ref "Q2") (pin "3") (pinfunction "C_3") (pintype "passive"))
    )
    (net (code "24") (name "Net-(IC1-(OC0A{slash}OC1C{slash}PCINT7)_PB7)") (class "Default")
      (node (ref "IC1") (pin "26") (pinfunction "(OC0A/OC1C/PCINT7)_PB7_26") (pintype "passive"))
      (node (ref "LED1") (pin "1") (pinfunction "A_1") (pintype "passive"))
    )
    (net (code "25") (name "Net-(IC1-(RXD0{slash}PCINT8)_PE0)") (class "Default")
      (node (ref "IC1") (pin "2") (pinfunction "(RXD0/PCINT8)_PE0_2") (pintype "passive"))
      (node (ref "R32") (pin "2") (pinfunction "2_2") (pintype "passive"))
    )
    (net (code "26") (name "Net-(IC1-(TXD0)_PE1)") (class "Default")
      (node (ref "IC1") (pin "3") (pinfunction "(TXD0)_PE1_3") (pintype "passive"))
      (node (ref "R30") (pin "2") (pinfunction "2_2") (pintype "passive"))
    )
    (net (code "27") (name "Net-(IC1-PF0_(ADC0))") (class "Default")
      (node (ref "IC1") (pin "97") (pinfunction "PF0_(ADC0)_97") (pintype "passive"))
      (node (ref "R28") (pin "2") (pinfunction "2_2") (pintype "passive"))
      (node (ref "Sensör Soketi1") (pin "1") (pintype "passive"))
    )
    (net (code "28") (name "Net-(IC1-PF1_(ADC1))") (class "Default")
      (node (ref "IC1") (pin "96") (pinfunction "PF1_(ADC1)_96") (pintype "passive"))
      (node (ref "R27") (pin "2") (pinfunction "2_2") (pintype "passive"))
      (node (ref "Sensör Soketi1") (pin "2") (pintype "passive"))
    )
    (net (code "29") (name "Net-(IC1-PF2_(ADC2))") (class "Default")
      (node (ref "IC1") (pin "95") (pinfunction "PF2_(ADC2)_95") (pintype "passive"))
      (node (ref "R26") (pin "2") (pinfunction "2_2") (pintype "passive"))
      (node (ref "Sensör Soketi1") (pin "3") (pintype "passive"))
    )
    (net (code "30") (name "Net-(IC1-PF3_(ADC3))") (class "Default")
      (node (ref "IC1") (pin "94") (pinfunction "PF3_(ADC3)_94") (pintype "passive"))
      (node (ref "R25") (pin "2") (pinfunction "2_2") (pintype "passive"))
      (node (ref "Sensör Soketi1") (pin "4") (pintype "passive"))
    )
    (net (code "31") (name "Net-(IC1-PF4_(ADC4{slash}TCK))") (class "Default")
      (node (ref "IC1") (pin "93") (pinfunction "PF4_(ADC4/TCK)_93") (pintype "passive"))
      (node (ref "R24") (pin "2") (pinfunction "2_2") (pintype "passive"))
      (node (ref "Sensör Soketi1") (pin "5") (pintype "passive"))
    )
    (net (code "32") (name "Net-(IC1-PF5_(ADC5{slash}TMS))") (class "Default")
      (node (ref "IC1") (pin "92") (pinfunction "PF5_(ADC5/TMS)_92") (pintype "passive"))
      (node (ref "R23") (pin "2") (pinfunction "2_2") (pintype "passive"))
      (node (ref "Sensör Soketi1") (pin "6") (pintype "passive"))
    )
    (net (code "33") (name "Net-(IC1-PF6_(ADC6{slash}TDO))") (class "Default")
      (node (ref "IC1") (pin "91") (pinfunction "PF6_(ADC6/TDO)_91") (pintype "passive"))
      (node (ref "R22") (pin "2") (pinfunction "2_2") (pintype "passive"))
      (node (ref "Sensör Soketi1") (pin "7") (pintype "passive"))
    )
    (net (code "34") (name "Net-(IC1-PF7_(ADC7{slash}TDI))") (class "Default")
      (node (ref "IC1") (pin "90") (pinfunction "PF7_(ADC7/TDI)_90") (pintype "passive"))
      (node (ref "R21") (pin "2") (pinfunction "2_2") (pintype "passive"))
      (node (ref "Sensör Soketi1") (pin "8") (pintype "passive"))
    )
    (net (code "35") (name "Net-(IC1-PK0_(ADC8{slash}PCINT16))") (class "Default")
      (node (ref "IC1") (pin "89") (pinfunction "PK0_(ADC8/PCINT16)_89") (pintype "passive"))
      (node (ref "R20") (pin "2") (pinfunction "2_2") (pintype "passive"))
      (node (ref "Sensör Soketi1") (pin "9") (pintype "passive"))
    )
    (net (code "36") (name "Net-(IC1-PK1_(ADC9{slash}PCINT17))") (class "Default")
      (node (ref "IC1") (pin "88") (pinfunction "PK1_(ADC9/PCINT17)_88") (pintype "passive"))
      (node (ref "R19") (pin "2") (pinfunction "2_2") (pintype "passive"))
      (node (ref "Sensör Soketi1") (pin "10") (pintype "passive"))
    )
    (net (code "37") (name "Net-(IC1-PK2_(ADC10{slash}PCINT18))") (class "Default")
      (node (ref "IC1") (pin "87") (pinfunction "PK2_(ADC10/PCINT18)_87") (pintype "passive"))
      (node (ref "R18") (pin "2") (pinfunction "2_2") (pintype "passive"))
      (node (ref "Sensör Soketi1") (pin "11") (pintype "passive"))
    )
    (net (code "38") (name "Net-(IC1-PK3_(ADC11{slash}PCINT19))") (class "Default")
      (node (ref "IC1") (pin "86") (pinfunction "PK3_(ADC11/PCINT19)_86") (pintype "passive"))
      (node (ref "R17") (pin "2") (pinfunction "2_2") (pintype "passive"))
      (node (ref "Sensör Soketi1") (pin "12") (pintype "passive"))
    )
    (net (code "39") (name "Net-(IC1-PK4_(ADC12{slash}PCINT20))") (class "Default")
      (node (ref "IC1") (pin "85") (pinfunction "PK4_(ADC12/PCINT20)_85") (pintype "passive"))
      (node (ref "R16") (pin "2") (pinfunction "2_2") (pintype "passive"))
      (node (ref "Sensör Soketi1") (pin "13") (pintype "passive"))
    )
    (net (code "40") (name "Net-(IC1-PK5_(ADC13{slash}PCINT21))") (class "Default")
      (node (ref "IC1") (pin "84") (pinfunction "PK5_(ADC13/PCINT21)_84") (pintype "passive"))
      (node (ref "R15") (pin "2") (pinfunction "2_2") (pintype "passive"))
      (node (ref "Sensör Soketi1") (pin "14") (pintype "passive"))
    )
    (net (code "41") (name "Net-(IC1-PK6_(ADC14{slash}PCINT22))") (class "Default")
      (node (ref "IC1") (pin "83") (pinfunction "PK6_(ADC14/PCINT22)_83") (pintype "passive"))
      (node (ref "R14") (pin "2") (pinfunction "2_2") (pintype "passive"))
      (node (ref "Sensör Soketi1") (pin "15") (pintype "passive"))
    )
    (net (code "42") (name "Net-(IC1-PK7_(ADC15{slash}PCINT23))") (class "Default")
      (node (ref "IC1") (pin "82") (pinfunction "PK7_(ADC15/PCINT23)_82") (pintype "passive"))
      (node (ref "R13") (pin "2") (pinfunction "2_2") (pintype "passive"))
      (node (ref "Sensör Soketi1") (pin "16") (pintype "passive"))
    )
    (net (code "43") (name "Net-(IC1-XTAL1)") (class "Default")
      (node (ref "C2") (pin "1") (pinfunction "1_1") (pintype "passive"))
      (node (ref "IC1") (pin "34") (pinfunction "XTAL1_34") (pintype "passive"))
      (node (ref "Y1") (pin "2") (pinfunction "2_2") (pintype "passive"))
    )
    (net (code "44") (name "Net-(IC1-XTAL2)") (class "Default")
      (node (ref "C3") (pin "1") (pinfunction "1_1") (pintype "passive"))
      (node (ref "IC1") (pin "33") (pinfunction "XTAL2_33") (pintype "passive"))
      (node (ref "Y1") (pin "1") (pinfunction "1_1") (pintype "passive"))
    )
    (net (code "45") (name "Net-(J1-Pad2)") (class "Default")
      (node (ref "J1") (pin "2") (pinfunction "2_2") (pintype "passive"))
      (node (ref "R5") (pin "2") (pinfunction "2_2") (pintype "passive"))
      (node (ref "R8") (pin "2") (pinfunction "2_2") (pintype "passive"))
    )
    (net (code "46") (name "Net-(J2-D+)") (class "Default")
      (node (ref "J2") (pin "3") (pinfunction "D+_3") (pintype "bidirectional"))
      (node (ref "U1") (pin "5") (pinfunction "UD+_5") (pintype "bidirectional"))
    )
    (net (code "47") (name "Net-(J2-D-)") (class "Default")
      (node (ref "J2") (pin "2") (pinfunction "D-_2") (pintype "bidirectional"))
      (node (ref "U1") (pin "6") (pinfunction "UD-_6") (pintype "bidirectional"))
    )
    (net (code "48") (name "Net-(LED1-K)") (class "Default")
      (node (ref "LED1") (pin "2") (pinfunction "K_2") (pintype "passive"))
      (node (ref "R29") (pin "1") (pinfunction "1_1") (pintype "passive"))
    )
    (net (code "49") (name "Net-(LED2-K)") (class "Default")
      (node (ref "LED2") (pin "2") (pinfunction "K_2") (pintype "passive"))
      (node (ref "R33") (pin "1") (pinfunction "1_1") (pintype "passive"))
    )
    (net (code "50") (name "Net-(LED3-A)") (class "Default")
      (node (ref "LED3") (pin "1") (pinfunction "A_1") (pintype "passive"))
      (node (ref "R37") (pin "1") (pinfunction "1_1") (pintype "passive"))
    )
    (net (code "51") (name "Net-(LED4-A)") (class "Default")
      (node (ref "LED4") (pin "1") (pinfunction "A_1") (pintype "passive"))
      (node (ref "R38") (pin "1") (pinfunction "1_1") (pintype "passive"))
    )
    (net (code "52") (name "Net-(OK1-A)") (class "Default")
      (node (ref "OK1") (pin "1") (pinfunction "A_1") (pintype "passive"))
      (node (ref "R36") (pin "2") (pinfunction "2_2") (pintype "passive"))
    )
    (net (code "53") (name "Net-(Q1-B)") (class "Default")
      (node (ref "Q1") (pin "1") (pinfunction "B_1") (pintype "passive"))
      (node (ref "R1") (pin "2") (pinfunction "2_2") (pintype "passive"))
      (node (ref "R2") (pin "2") (pinfunction "2_2") (pintype "passive"))
    )
    (net (code "54") (name "Net-(Q2-B)") (class "Default")
      (node (ref "Q2") (pin "1") (pinfunction "B_1") (pintype "passive"))
      (node (ref "R3") (pin "2") (pinfunction "2_2") (pintype "passive"))
      (node (ref "R6") (pin "2") (pinfunction "2_2") (pintype "passive"))
    )
    (net (code "55") (name "Net-(Q3-B)") (class "Default")
      (node (ref "Q3") (pin "1") (pinfunction "B_1") (pintype "passive"))
      (node (ref "R4") (pin "2") (pinfunction "2_2") (pintype "passive"))
      (node (ref "R7") (pin "2") (pinfunction "2_2") (pintype "passive"))
    )
    (net (code "56") (name "Net-(Q4-B)") (class "Default")
      (node (ref "Q4") (pin "1") (pinfunction "B_1") (pintype "passive"))
      (node (ref "R10") (pin "2") (pinfunction "2_2") (pintype "passive"))
      (node (ref "R9") (pin "1") (pinfunction "1_1") (pintype "passive"))
    )
    (net (code "57") (name "Net-(Q4-E)") (class "Default")
      (node (ref "Q4") (pin "2") (pinfunction "E_2") (pintype "passive"))
      (node (ref "Sensör Soketi1") (pin "18") (pintype "passive"))
    )
    (net (code "58") (name "Net-(Q5-B)") (class "Default")
      (node (ref "Q5") (pin "1") (pinfunction "B_1") (pintype "passive"))
      (node (ref "R12") (pin "2") (pinfunction "2_2") (pintype "passive"))
    )
    (net (code "59") (name "Net-(Q5-C)") (class "Default")
      (node (ref "Q5") (pin "3") (pinfunction "C_3") (pintype "passive"))
      (node (ref "R10") (pin "1") (pinfunction "1_1") (pintype "passive"))
    )
    (net (code "60") (name "Net-(Q6-B)") (class "Default")
      (node (ref "Q6") (pin "1") (pinfunction "B_1") (pintype "passive"))
      (node (ref "R34") (pin "2") (pinfunction "2_2") (pintype "passive"))
    )
    (net (code "61") (name "Net-(Q6-C)") (class "Default")
      (node (ref "B1") (pin "2") (pinfunction "2_2") (pintype "passive"))
      (node (ref "Q6") (pin "3") (pinfunction "C_3") (pintype "passive"))
      (node (ref "R31") (pin "1") (pinfunction "1_1") (pintype "passive"))
    )
    (net (code "62") (name "Net-(U1-V3)") (class "Default")
      (node (ref "C7") (pin "1") (pinfunction "1_1") (pintype "passive"))
      (node (ref "U1") (pin "4") (pinfunction "V3_4") (pintype "power_in"))
    )
    (net (code "63") (name "Net-(U1-XI)") (class "Default")
      (node (ref "C8") (pin "2") (pinfunction "2_2") (pintype "passive"))
      (node (ref "U1") (pin "7") (pinfunction "XI_7") (pintype "input"))
      (node (ref "Y2") (pin "2") (pinfunction "2_2") (pintype "passive"))
    )
    (net (code "64") (name "Net-(U1-XO)") (class "Default")
      (node (ref "C9") (pin "2") (pinfunction "2_2") (pintype "passive"))
      (node (ref "U1") (pin "8") (pinfunction "XO_8") (pintype "output"))
      (node (ref "Y2") (pin "1") (pinfunction "1_1") (pintype "passive"))
    )
    (net (code "65") (name "unconnected-(AnahatR.1-NC-Pad1)") (class "Default")
      (node (ref "AnahatR.1") (pin "1") (pinfunction "NC_1") (pintype "passive"))
    )
    (net (code "66") (name "unconnected-(Dortlu1-NC-Pad1)") (class "Default")
      (node (ref "Dortlu1") (pin "1") (pinfunction "NC_1") (pintype "passive"))
    )
    (net (code "67") (name "unconnected-(IC1-(CLKO{slash}ICP3{slash}INT7)_PE7-Pad9)") (class "Default")
      (node (ref "IC1") (pin "9") (pinfunction "(CLKO/ICP3/INT7)_PE7_9") (pintype "passive"))
    )
    (net (code "68") (name "unconnected-(IC1-(ICP1)_PD4-Pad47)") (class "Default")
      (node (ref "IC1") (pin "47") (pinfunction "(ICP1)_PD4_47") (pintype "passive"))
    )
    (net (code "69") (name "unconnected-(IC1-(ICP4)_PL0-Pad35)") (class "Default")
      (node (ref "IC1") (pin "35") (pinfunction "(ICP4)_PL0_35") (pintype "passive"))
    )
    (net (code "70") (name "unconnected-(IC1-(ICP5)_PL1-Pad36)") (class "Default")
      (node (ref "IC1") (pin "36") (pinfunction "(ICP5)_PL1_36") (pintype "passive"))
    )
    (net (code "71") (name "unconnected-(IC1-(MISO{slash}PCINT3)_PB3-Pad22)") (class "Default")
      (node (ref "IC1") (pin "22") (pinfunction "(MISO/PCINT3)_PB3_22") (pintype "passive"))
    )
    (net (code "72") (name "unconnected-(IC1-(MOSI{slash}PCINT2)_PB2-Pad21)") (class "Default")
      (node (ref "IC1") (pin "21") (pinfunction "(MOSI/PCINT2)_PB2_21") (pintype "passive"))
    )
    (net (code "73") (name "unconnected-(IC1-(OC2A{slash}PCINT4)_PB4-Pad23)") (class "Default")
      (node (ref "IC1") (pin "23") (pinfunction "(OC2A/PCINT4)_PB4_23") (pintype "passive"))
    )
    (net (code "74") (name "unconnected-(IC1-(OC4B)_PH4-Pad16)") (class "Default")
      (node (ref "IC1") (pin "16") (pinfunction "(OC4B)_PH4_16") (pintype "passive"))
    )
    (net (code "75") (name "unconnected-(IC1-(OC5A)_PL3-Pad38)") (class "Default")
      (node (ref "IC1") (pin "38") (pinfunction "(OC5A)_PL3_38") (pintype "passive"))
    )
    (net (code "76") (name "unconnected-(IC1-(OC5B)_PL4-Pad39)") (class "Default")
      (node (ref "IC1") (pin "39") (pinfunction "(OC5B)_PL4_39") (pintype "passive"))
    )
    (net (code "77") (name "unconnected-(IC1-(OC5C)_PL5-Pad40)") (class "Default")
      (node (ref "IC1") (pin "40") (pinfunction "(OC5C)_PL5_40") (pintype "passive"))
    )
    (net (code "78") (name "unconnected-(IC1-(RXD1{slash}INT2)_PD2-Pad45)") (class "Default")
      (node (ref "IC1") (pin "45") (pinfunction "(RXD1/INT2)_PD2_45") (pintype "passive"))
    )
    (net (code "79") (name "unconnected-(IC1-(RXD2)_PH0-Pad12)") (class "Default")
      (node (ref "IC1") (pin "12") (pinfunction "(RXD2)_PH0_12") (pintype "passive"))
    )
    (net (code "80") (name "unconnected-(IC1-(SCK{slash}PCINT1)_PB1-Pad20)") (class "Default")
      (node (ref "IC1") (pin "20") (pinfunction "(SCK/PCINT1)_PB1_20") (pintype "passive"))
    )
    (net (code "81") (name "unconnected-(IC1-(SCL{slash}INT0)_PD0-Pad43)") (class "Default")
      (node (ref "IC1") (pin "43") (pinfunction "(SCL/INT0)_PD0_43") (pintype "passive"))
    )
    (net (code "82") (name "unconnected-(IC1-(SDA{slash}INT1)_PD1-Pad44)") (class "Default")
      (node (ref "IC1") (pin "44") (pinfunction "(SDA/INT1)_PD1_44") (pintype "passive"))
    )
    (net (code "83") (name "unconnected-(IC1-(T0)_PD7-Pad50)") (class "Default")
      (node (ref "IC1") (pin "50") (pinfunction "(T0)_PD7_50") (pintype "passive"))
    )
    (net (code "84") (name "unconnected-(IC1-(T1)_PD6-Pad49)") (class "Default")
      (node (ref "IC1") (pin "49") (pinfunction "(T1)_PD6_49") (pintype "passive"))
    )
    (net (code "85") (name "unconnected-(IC1-(T3{slash}INT6)_PE6-Pad8)") (class "Default")
      (node (ref "IC1") (pin "8") (pinfunction "(T3/INT6)_PE6_8") (pintype "passive"))
    )
    (net (code "86") (name "unconnected-(IC1-(T4)_PH7-Pad27)") (class "Default")
      (node (ref "IC1") (pin "27") (pinfunction "(T4)_PH7_27") (pintype "passive"))
    )
    (net (code "87") (name "unconnected-(IC1-(T5)_PL2-Pad37)") (class "Default")
      (node (ref "IC1") (pin "37") (pinfunction "(T5)_PL2_37") (pintype "passive"))
    )
    (net (code "88") (name "unconnected-(IC1-(TOSC1)_PG4-Pad29)") (class "Default")
      (node (ref "IC1") (pin "29") (pinfunction "(TOSC1)_PG4_29") (pintype "passive"))
    )
    (net (code "89") (name "unconnected-(IC1-(TOSC2)_PG3-Pad28)") (class "Default")
      (node (ref "IC1") (pin "28") (pinfunction "(TOSC2)_PG3_28") (pintype "passive"))
    )
    (net (code "90") (name "unconnected-(IC1-(TXD1{slash}INT3)_PD3-Pad46)") (class "Default")
      (node (ref "IC1") (pin "46") (pinfunction "(TXD1/INT3)_PD3_46") (pintype "passive"))
    )
    (net (code "91") (name "unconnected-(IC1-(TXD2)_PH1-Pad13)") (class "Default")
      (node (ref "IC1") (pin "13") (pinfunction "(TXD2)_PH1_13") (pintype "passive"))
    )
    (net (code "92") (name "unconnected-(IC1-(XCK0{slash}AIN0)_PE2-Pad4)") (class "Default")
      (node (ref "IC1") (pin "4") (pinfunction "(XCK0/AIN0)_PE2_4") (pintype "passive"))
    )
    (net (code "93") (name "unconnected-(IC1-(XCK1)_PD5-Pad48)") (class "Default")
      (node (ref "IC1") (pin "48") (pinfunction "(XCK1)_PD5_48") (pintype "passive"))
    )
    (net (code "94") (name "unconnected-(IC1-(XCK2)_PH2-Pad14)") (class "Default")
      (node (ref "IC1") (pin "14") (pinfunction "(XCK2)_PH2_14") (pintype "passive"))
    )
    (net (code "95") (name "unconnected-(IC1-(~{SS}{slash}PCINT0)_PB0-Pad19)") (class "Default")
      (node (ref "IC1") (pin "19") (pinfunction "(~{SS}/PCINT0)_PB0_19") (pintype "passive"))
    )
    (net (code "96") (name "unconnected-(IC1-PA0_(AD0)-Pad78)") (class "Default")
      (node (ref "IC1") (pin "78") (pinfunction "PA0_(AD0)_78") (pintype "passive"))
    )
    (net (code "97") (name "unconnected-(IC1-PA1_(AD1)-Pad77)") (class "Default")
      (node (ref "IC1") (pin "77") (pinfunction "PA1_(AD1)_77") (pintype "passive"))
    )
    (net (code "98") (name "unconnected-(IC1-PA2_(AD2)-Pad76)") (class "Default")
      (node (ref "IC1") (pin "76") (pinfunction "PA2_(AD2)_76") (pintype "passive"))
    )
    (net (code "99") (name "unconnected-(IC1-PA3_(AD3)-Pad75)") (class "Default")
      (node (ref "IC1") (pin "75") (pinfunction "PA3_(AD3)_75") (pintype "passive"))
    )
    (net (code "100") (name "unconnected-(IC1-PA4_(AD4)-Pad74)") (class "Default")
      (node (ref "IC1") (pin "74") (pinfunction "PA4_(AD4)_74") (pintype "passive"))
    )
    (net (code "101") (name "unconnected-(IC1-PA5_(AD5)-Pad73)") (class "Default")
      (node (ref "IC1") (pin "73") (pinfunction "PA5_(AD5)_73") (pintype "passive"))
    )
    (net (code "102") (name "unconnected-(IC1-PA6_(AD6)-Pad72)") (class "Default")
      (node (ref "IC1") (pin "72") (pinfunction "PA6_(AD6)_72") (pintype "passive"))
    )
    (net (code "103") (name "unconnected-(IC1-PC0_(A8)-Pad53)") (class "Default")
      (node (ref "IC1") (pin "53") (pinfunction "PC0_(A8)_53") (pintype "passive"))
    )
    (net (code "104") (name "unconnected-(IC1-PC1_(A9)-Pad54)") (class "Default")
      (node (ref "IC1") (pin "54") (pinfunction "PC1_(A9)_54") (pintype "passive"))
    )
    (net (code "105") (name "unconnected-(IC1-PC2_(A10)-Pad55)") (class "Default")
      (node (ref "IC1") (pin "55") (pinfunction "PC2_(A10)_55") (pintype "passive"))
    )
    (net (code "106") (name "unconnected-(IC1-PC3_(A11)-Pad56)") (class "Default")
      (node (ref "IC1") (pin "56") (pinfunction "PC3_(A11)_56") (pintype "passive"))
    )
    (net (code "107") (name "unconnected-(IC1-PC4_(A12)-Pad57)") (class "Default")
      (node (ref "IC1") (pin "57") (pinfunction "PC4_(A12)_57") (pintype "passive"))
    )
    (net (code "108") (name "unconnected-(IC1-PC5_(A13)-Pad58)") (class "Default")
      (node (ref "IC1") (pin "58") (pinfunction "PC5_(A13)_58") (pintype "passive"))
    )
    (net (code "109") (name "unconnected-(IC1-PC6_(A14)-Pad59)") (class "Default")
      (node (ref "IC1") (pin "59") (pinfunction "PC6_(A14)_59") (pintype "passive"))
    )
    (net (code "110") (name "unconnected-(IC1-PC7_(A15)-Pad60)") (class "Default")
      (node (ref "IC1") (pin "60") (pinfunction "PC7_(A15)_60") (pintype "passive"))
    )
    (net (code "111") (name "unconnected-(IC1-PG0_(~{WR)}-Pad51)") (class "Default")
      (node (ref "IC1") (pin "51") (pinfunction "PG0_(~{WR)}_51") (pintype "passive"))
    )
    (net (code "112") (name "unconnected-(IC1-PG1_(~{RD)}-Pad52)") (class "Default")
      (node (ref "IC1") (pin "52") (pinfunction "PG1_(~{RD)}_52") (pintype "passive"))
    )
    (net (code "113") (name "unconnected-(IC1-PG2_(ALE)-Pad70)") (class "Default")
      (node (ref "IC1") (pin "70") (pinfunction "PG2_(ALE)_70") (pintype "passive"))
    )
    (net (code "114") (name "unconnected-(IC1-PJ0_(RXD3{slash}PCINT9)-Pad63)") (class "Default")
      (node (ref "IC1") (pin "63") (pinfunction "PJ0_(RXD3/PCINT9)_63") (pintype "passive"))
    )
    (net (code "115") (name "unconnected-(IC1-PJ1_(TXD3{slash}PCINT10)-Pad64)") (class "Default")
      (node (ref "IC1") (pin "64") (pinfunction "PJ1_(TXD3/PCINT10)_64") (pintype "passive"))
    )
    (net (code "116") (name "unconnected-(IC1-PJ2_(XCK3{slash}PCINT11)-Pad65)") (class "Default")
      (node (ref "IC1") (pin "65") (pinfunction "PJ2_(XCK3/PCINT11)_65") (pintype "passive"))
    )
    (net (code "117") (name "unconnected-(IC1-PJ3_(PCINT12)-Pad66)") (class "Default")
      (node (ref "IC1") (pin "66") (pinfunction "PJ3_(PCINT12)_66") (pintype "passive"))
    )
    (net (code "118") (name "unconnected-(IC1-PJ4_(PCINT13)-Pad67)") (class "Default")
      (node (ref "IC1") (pin "67") (pinfunction "PJ4_(PCINT13)_67") (pintype "passive"))
    )
    (net (code "119") (name "unconnected-(IC1-PJ5_(PCINT14)-Pad68)") (class "Default")
      (node (ref "IC1") (pin "68") (pinfunction "PJ5_(PCINT14)_68") (pintype "passive"))
    )
    (net (code "120") (name "unconnected-(IC1-PJ6_(PCINT15)-Pad69)") (class "Default")
      (node (ref "IC1") (pin "69") (pinfunction "PJ6_(PCINT15)_69") (pintype "passive"))
    )
    (net (code "121") (name "unconnected-(IC1-PJ7-Pad79)") (class "Default")
      (node (ref "IC1") (pin "79") (pinfunction "PJ7_79") (pintype "passive"))
    )
    (net (code "122") (name "unconnected-(IC1-PL6-Pad41)") (class "Default")
      (node (ref "IC1") (pin "41") (pinfunction "PL6_41") (pintype "passive"))
    )
    (net (code "123") (name "unconnected-(IC1-PL7-Pad42)") (class "Default")
      (node (ref "IC1") (pin "42") (pinfunction "PL7_42") (pintype "passive"))
    )
    (net (code "124") (name "unconnected-(KornaR1-NC-Pad1)") (class "Default")
      (node (ref "KornaR1") (pin "1") (pinfunction "NC_1") (pintype "passive"))
    )
    (net (code "125") (name "unconnected-(OK1-BAS-Pad6)") (class "Default")
      (node (ref "OK1") (pin "6") (pinfunction "BAS_6") (pintype "passive"))
    )
    (net (code "126") (name "unconnected-(S1-COM_2-Pad3)") (class "Default")
      (node (ref "S1") (pin "3") (pinfunction "COM_2_3") (pintype "passive+no_connect"))
    )
    (net (code "127") (name "unconnected-(S1-NO_2-Pad4)") (class "Default")
      (node (ref "S1") (pin "4") (pinfunction "NO_2_4") (pintype "passive+no_connect"))
    )
    (net (code "128") (name "unconnected-(U1-RS232-Pad15)") (class "Default")
      (node (ref "U1") (pin "15") (pinfunction "RS232_15") (pintype "input+no_connect"))
    )
    (net (code "129") (name "unconnected-(U1-~{CTS}-Pad9)") (class "Default")
      (node (ref "U1") (pin "9") (pinfunction "~{CTS}_9") (pintype "input+no_connect"))
    )
    (net (code "130") (name "unconnected-(U1-~{DCD}-Pad12)") (class "Default")
      (node (ref "U1") (pin "12") (pinfunction "~{DCD}_12") (pintype "input+no_connect"))
    )
    (net (code "131") (name "unconnected-(U1-~{DSR}-Pad10)") (class "Default")
      (node (ref "U1") (pin "10") (pinfunction "~{DSR}_10") (pintype "input+no_connect"))
    )
    (net (code "132") (name "unconnected-(U1-~{RI}-Pad11)") (class "Default")
      (node (ref "U1") (pin "11") (pinfunction "~{RI}_11") (pintype "input+no_connect"))
    )
    (net (code "133") (name "unconnected-(U1-~{RTS}-Pad14)") (class "Default")
      (node (ref "U1") (pin "14") (pinfunction "~{RTS}_14") (pintype "output+no_connect"))
    )
  )
)
